# BMS_AFE.net
KiCad netlist of a schematic drawn in Altium Designer
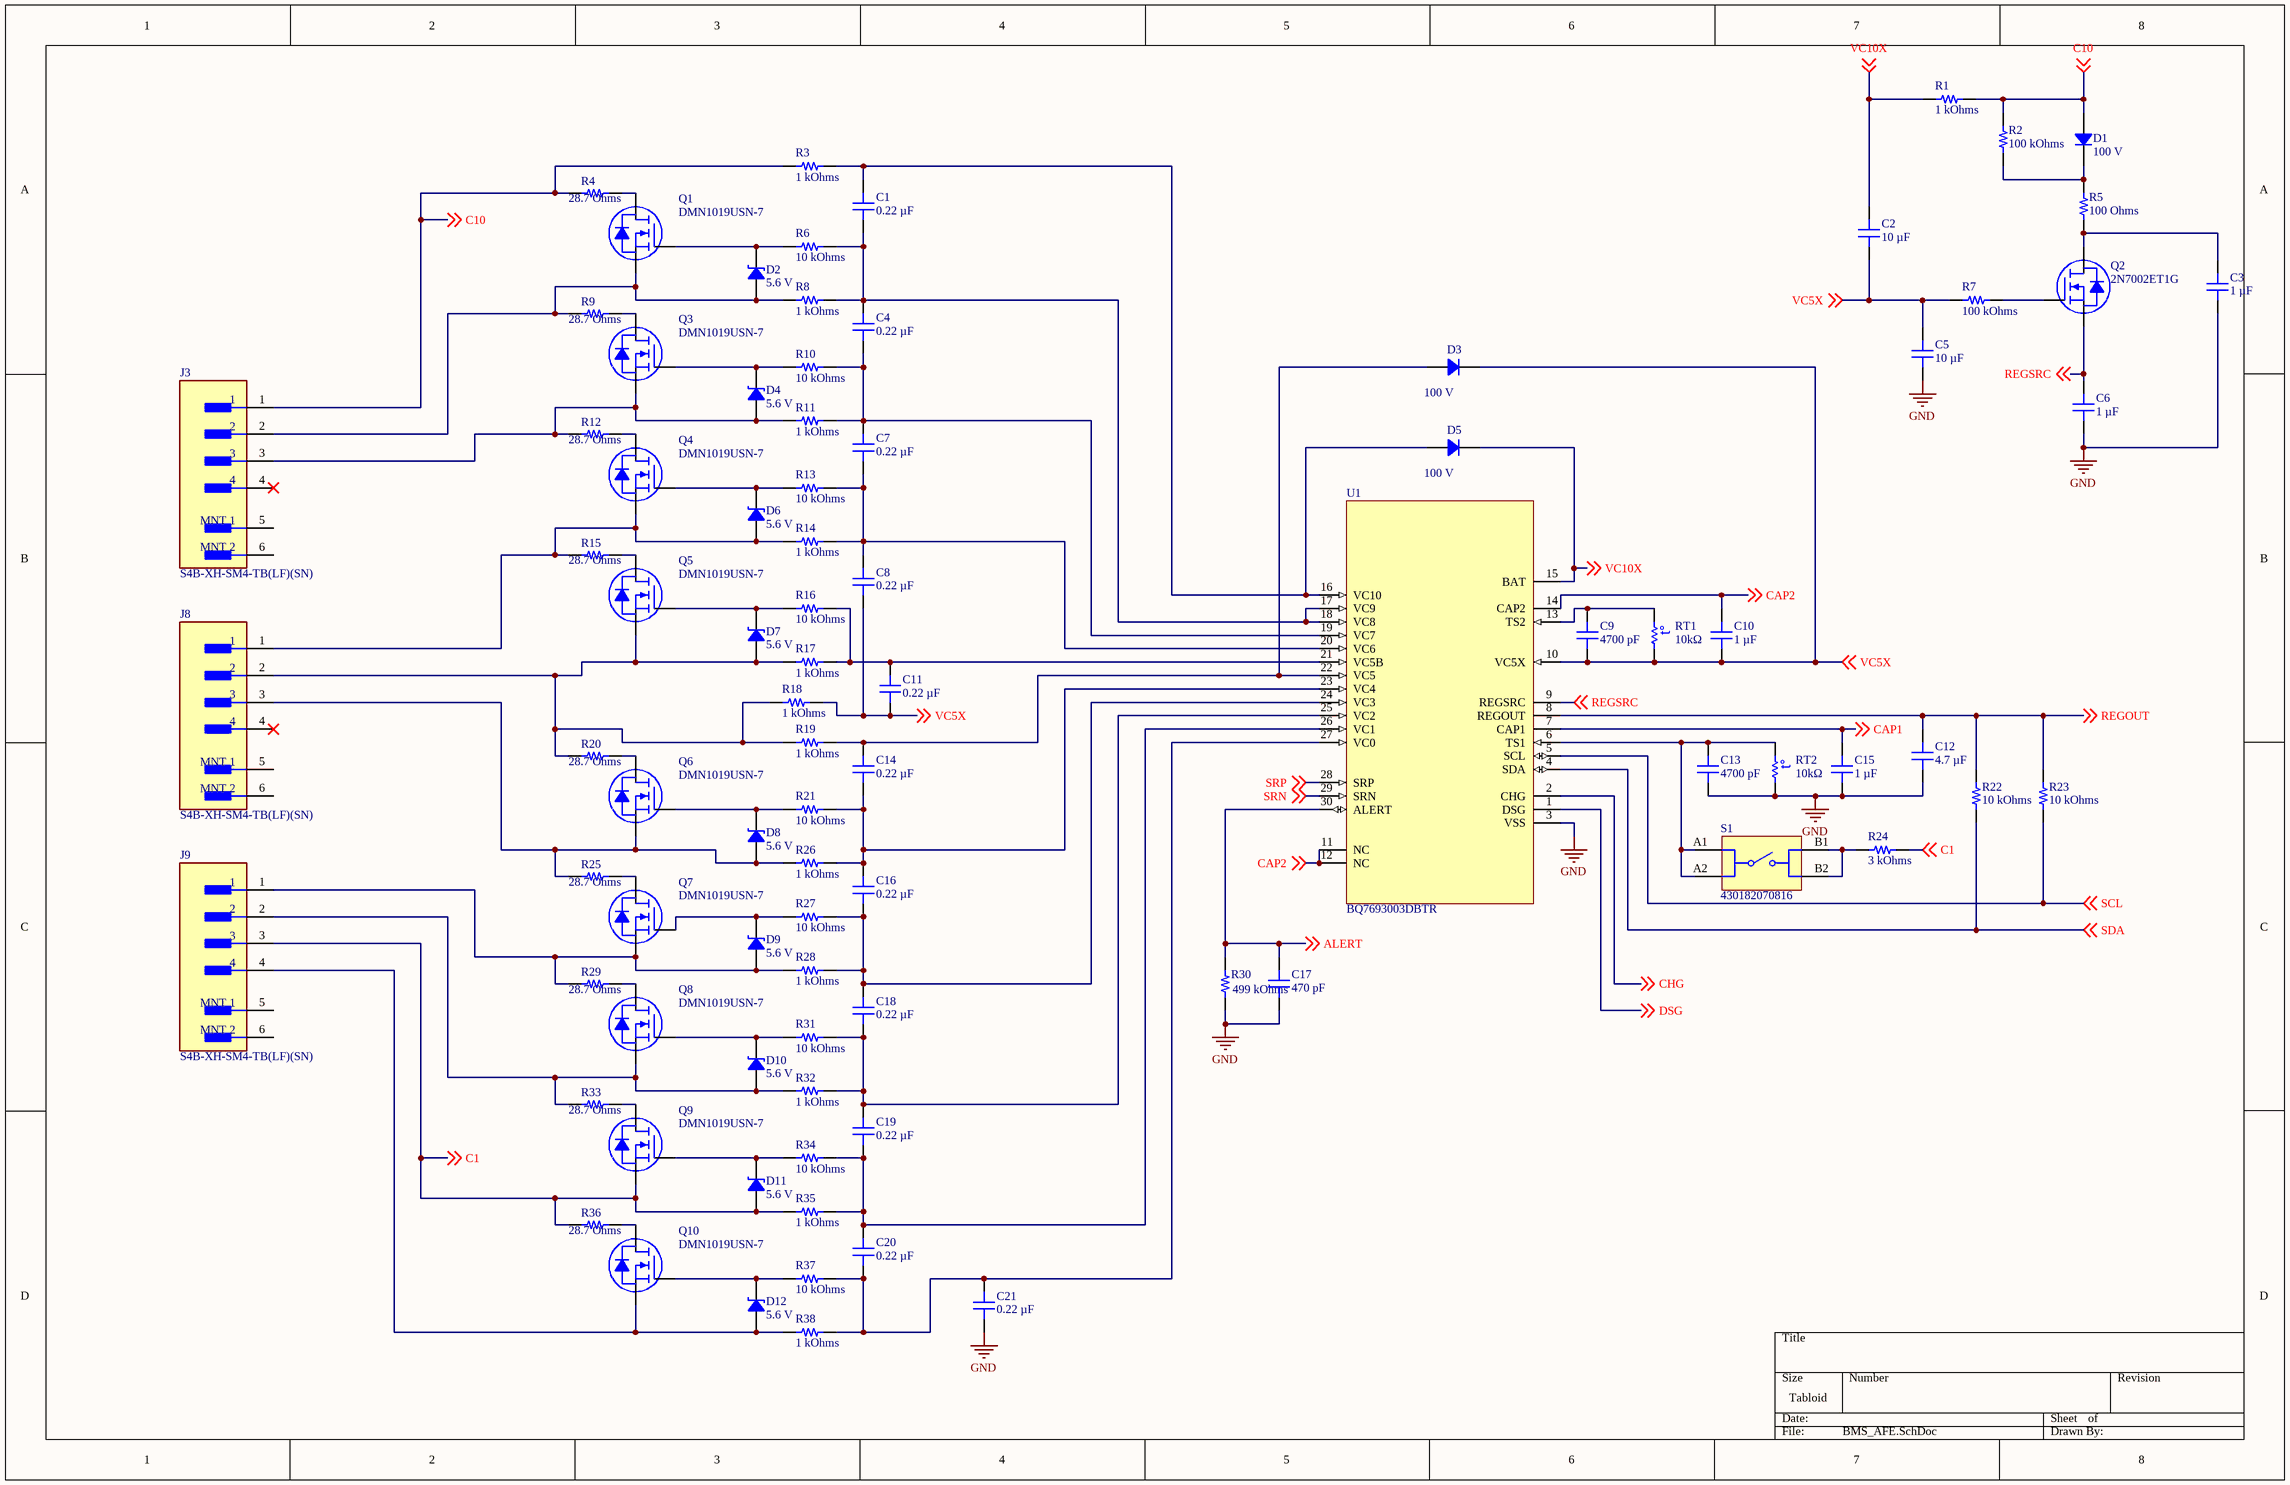
[diagram p0: BMS_AFE.SchDoc]

(export (version "E")
  (design (tool "Eeschema 10.0.6"))
  (components
    (comp (ref "C1")
      (value "0.22 µF")
      (footprint "CAP 0603_1608")
      (description "CAP CER 0.22UF 16V X7R 0603")
      (fields
        (field (name "PART NUMBER") "885012206048")
        (field (name "CAPACITANCE") "0.22 µF")
        (field (name "MANUFACTURER") "Würth Elektronik")
      )
      (libsource (lib "Celestial Altium Library - altium_library") (part "Capacitor"))
    )
    (comp (ref "C2")
      (value "10 µF")
      (footprint "CAP 1210_3225 - 1MM")
      (description "CAP CER 10UF 35V X7R 1210")
      (fields
        (field (name "PART NUMBER") "CL32B106KLJNNNE")
        (field (name "MANUFACTURER") "Samsung Electro-Mechanics")
      )
      (libsource (lib "Celestial Altium Library - altium_library") (part "Capacitor"))
    )
    (comp (ref "C3")
      (value "1 µF")
      (footprint "CAP 0805_2012")
      (description "CAP CER 1UF 50V X7R 0805")
      (fields
        (field (name "PART NUMBER") "GCJ21BR71H105KA01L")
        (field (name "CAPACITANCE") "1 µF")
        (field (name "MANUFACTURER") "Murata Electronics")
      )
      (libsource (lib "Celestial Altium Library - altium_library") (part "Capacitor"))
    )
    (comp (ref "C4")
      (value "0.22 µF")
      (footprint "CAP 0603_1608")
      (description "CAP CER 0.22UF 16V X7R 0603")
      (fields
        (field (name "PART NUMBER") "885012206048")
        (field (name "CAPACITANCE") "0.22 µF")
        (field (name "MANUFACTURER") "Würth Elektronik")
      )
      (libsource (lib "Celestial Altium Library - altium_library") (part "Capacitor"))
    )
    (comp (ref "C5")
      (value "10 µF")
      (footprint "CAP 1210_3225 - 1MM")
      (description "CAP CER 10UF 35V X7R 1210")
      (fields
        (field (name "PART NUMBER") "CL32B106KLJNNNE")
        (field (name "MANUFACTURER") "Samsung Electro-Mechanics")
      )
      (libsource (lib "Celestial Altium Library - altium_library") (part "Capacitor"))
    )
    (comp (ref "C6")
      (value "1 µF")
      (footprint "CAP 0805_2012")
      (description "CAP CER 1UF 50V X7R 0805")
      (fields
        (field (name "PART NUMBER") "GCJ21BR71H105KA01L")
        (field (name "CAPACITANCE") "1 µF")
        (field (name "MANUFACTURER") "Murata Electronics")
      )
      (libsource (lib "Celestial Altium Library - altium_library") (part "Capacitor"))
    )
    (comp (ref "C7")
      (value "0.22 µF")
      (footprint "CAP 0603_1608")
      (description "CAP CER 0.22UF 16V X7R 0603")
      (fields
        (field (name "PART NUMBER") "885012206048")
        (field (name "CAPACITANCE") "0.22 µF")
        (field (name "MANUFACTURER") "Würth Elektronik")
      )
      (libsource (lib "Celestial Altium Library - altium_library") (part "Capacitor"))
    )
    (comp (ref "C8")
      (value "0.22 µF")
      (footprint "CAP 0603_1608")
      (description "CAP CER 0.22UF 16V X7R 0603")
      (fields
        (field (name "PART NUMBER") "885012206048")
        (field (name "CAPACITANCE") "0.22 µF")
        (field (name "MANUFACTURER") "Würth Elektronik")
      )
      (libsource (lib "Celestial Altium Library - altium_library") (part "Capacitor"))
    )
    (comp (ref "C9")
      (value "4700 pF")
      (footprint "CAP 0603_1608")
      (description "CAP CER 4700PF 50V X7R 0603")
      (fields
        (field (name "PART NUMBER") "885012206087")
        (field (name "CAPACITANCE") "4700 pF")
        (field (name "MANUFACTURER") "Würth Elektronik")
      )
      (libsource (lib "Celestial Altium Library - altium_library") (part "Capacitor"))
    )
    (comp (ref "C10")
      (value "1 µF")
      (footprint "CAP 0603_1608")
      (description "CAP CER 1UF 16V X7R 0603")
      (fields
        (field (name "PART NUMBER") "885012206052")
        (field (name "CAPACITANCE") "1 µF")
        (field (name "MANUFACTURER") "Würth Elektronik")
      )
      (libsource (lib "Celestial Altium Library - altium_library") (part "Capacitor"))
    )
    (comp (ref "C11")
      (value "0.22 µF")
      (footprint "CAP 0603_1608")
      (description "CAP CER 0.22UF 16V X7R 0603")
      (fields
        (field (name "PART NUMBER") "885012206048")
        (field (name "CAPACITANCE") "0.22 µF")
        (field (name "MANUFACTURER") "Würth Elektronik")
      )
      (libsource (lib "Celestial Altium Library - altium_library") (part "Capacitor"))
    )
    (comp (ref "C12")
      (value "4.7 µF")
      (footprint "CAP 0805_2012")
      (description "CAP CER 4.7UF 10V X7R 0805")
      (fields
        (field (name "PART NUMBER") "885012207025")
        (field (name "CAPACITANCE") "4.7 µF")
        (field (name "MANUFACTURER") "Würth Elektronik")
      )
      (libsource (lib "Celestial Altium Library - altium_library") (part "Capacitor"))
    )
    (comp (ref "C13")
      (value "4700 pF")
      (footprint "CAP 0603_1608")
      (description "CAP CER 4700PF 50V X7R 0603")
      (fields
        (field (name "PART NUMBER") "885012206087")
        (field (name "CAPACITANCE") "4700 pF")
        (field (name "MANUFACTURER") "Würth Elektronik")
      )
      (libsource (lib "Celestial Altium Library - altium_library") (part "Capacitor"))
    )
    (comp (ref "C14")
      (value "0.22 µF")
      (footprint "CAP 0603_1608")
      (description "CAP CER 0.22UF 16V X7R 0603")
      (fields
        (field (name "PART NUMBER") "885012206048")
        (field (name "CAPACITANCE") "0.22 µF")
        (field (name "MANUFACTURER") "Würth Elektronik")
      )
      (libsource (lib "Celestial Altium Library - altium_library") (part "Capacitor"))
    )
    (comp (ref "C15")
      (value "1 µF")
      (footprint "CAP 0603_1608")
      (description "CAP CER 1UF 16V X7R 0603")
      (fields
        (field (name "PART NUMBER") "885012206052")
        (field (name "CAPACITANCE") "1 µF")
        (field (name "MANUFACTURER") "Würth Elektronik")
      )
      (libsource (lib "Celestial Altium Library - altium_library") (part "Capacitor"))
    )
    (comp (ref "C16")
      (value "0.22 µF")
      (footprint "CAP 0603_1608")
      (description "CAP CER 0.22UF 16V X7R 0603")
      (fields
        (field (name "PART NUMBER") "885012206048")
        (field (name "CAPACITANCE") "0.22 µF")
        (field (name "MANUFACTURER") "Würth Elektronik")
      )
      (libsource (lib "Celestial Altium Library - altium_library") (part "Capacitor"))
    )
    (comp (ref "C17")
      (value "470 pF")
      (footprint "CAP 0603_1608")
      (description "CAP CER 470PF 50V X7R 0603")
      (fields
        (field (name "PART NUMBER") "885012206081")
        (field (name "CAPACITANCE") "470 pF")
        (field (name "MANUFACTURER") "Würth Elektronik")
      )
      (libsource (lib "Celestial Altium Library - altium_library") (part "Capacitor"))
    )
    (comp (ref "C18")
      (value "0.22 µF")
      (footprint "CAP 0603_1608")
      (description "CAP CER 0.22UF 16V X7R 0603")
      (fields
        (field (name "PART NUMBER") "885012206048")
        (field (name "CAPACITANCE") "0.22 µF")
        (field (name "MANUFACTURER") "Würth Elektronik")
      )
      (libsource (lib "Celestial Altium Library - altium_library") (part "Capacitor"))
    )
    (comp (ref "C19")
      (value "0.22 µF")
      (footprint "CAP 0603_1608")
      (description "CAP CER 0.22UF 16V X7R 0603")
      (fields
        (field (name "PART NUMBER") "885012206048")
        (field (name "CAPACITANCE") "0.22 µF")
        (field (name "MANUFACTURER") "Würth Elektronik")
      )
      (libsource (lib "Celestial Altium Library - altium_library") (part "Capacitor"))
    )
    (comp (ref "C20")
      (value "0.22 µF")
      (footprint "CAP 0603_1608")
      (description "CAP CER 0.22UF 16V X7R 0603")
      (fields
        (field (name "PART NUMBER") "885012206048")
        (field (name "CAPACITANCE") "0.22 µF")
        (field (name "MANUFACTURER") "Würth Elektronik")
      )
      (libsource (lib "Celestial Altium Library - altium_library") (part "Capacitor"))
    )
    (comp (ref "C21")
      (value "0.22 µF")
      (footprint "CAP 0603_1608")
      (description "CAP CER 0.22UF 16V X7R 0603")
      (fields
        (field (name "PART NUMBER") "885012206048")
        (field (name "CAPACITANCE") "0.22 µF")
        (field (name "MANUFACTURER") "Würth Elektronik")
      )
      (libsource (lib "Celestial Altium Library - altium_library") (part "Capacitor"))
    )
    (comp (ref "D1")
      (value "1N4148W-7-F")
      (footprint "SOD-123")
      (description "DIODE GEN PURP 100V 300MA SOD123")
      (fields
        (field (name "MANUFACTURER") "Diodes Incorporated")
        (field (name "VOLTAGE - DC REVERSE (VR) (MAX)") "100 V")
      )
      (libsource (lib "Celestial Altium Library - altium_library") (part "Diode"))
    )
    (comp (ref "D2")
      (value "MMSZ5232BS-7-F")
      (footprint "SOD323")
      (description "DIODE ZENER 5.6V 200MW SOD323")
      (fields
        (field (name "MANUFACTURER") "Diodes Incorporated")
        (field (name "TOLERANCE") "±5%")
        (field (name "VOLTAGE - ZENER (NOM) (VZ)") "5.6 V")
      )
      (libsource (lib "Celestial Altium Library - altium_library") (part "Diode Zener"))
    )
    (comp (ref "D3")
      (value "1N4148W-7-F")
      (footprint "SOD-123")
      (description "DIODE GEN PURP 100V 300MA SOD123")
      (fields
        (field (name "MANUFACTURER") "Diodes Incorporated")
        (field (name "VOLTAGE - DC REVERSE (VR) (MAX)") "100 V")
      )
      (libsource (lib "Celestial Altium Library - altium_library") (part "Diode"))
    )
    (comp (ref "D4")
      (value "MMSZ5232BS-7-F")
      (footprint "SOD323")
      (description "DIODE ZENER 5.6V 200MW SOD323")
      (fields
        (field (name "MANUFACTURER") "Diodes Incorporated")
        (field (name "TOLERANCE") "±5%")
        (field (name "VOLTAGE - ZENER (NOM) (VZ)") "5.6 V")
      )
      (libsource (lib "Celestial Altium Library - altium_library") (part "Diode Zener"))
    )
    (comp (ref "D5")
      (value "1N4148W-7-F")
      (footprint "SOD-123")
      (description "DIODE GEN PURP 100V 300MA SOD123")
      (fields
        (field (name "MANUFACTURER") "Diodes Incorporated")
        (field (name "VOLTAGE - DC REVERSE (VR) (MAX)") "100 V")
      )
      (libsource (lib "Celestial Altium Library - altium_library") (part "Diode"))
    )
    (comp (ref "D6")
      (value "MMSZ5232BS-7-F")
      (footprint "SOD323")
      (description "DIODE ZENER 5.6V 200MW SOD323")
      (fields
        (field (name "MANUFACTURER") "Diodes Incorporated")
        (field (name "TOLERANCE") "±5%")
        (field (name "VOLTAGE - ZENER (NOM) (VZ)") "5.6 V")
      )
      (libsource (lib "Celestial Altium Library - altium_library") (part "Diode Zener"))
    )
    (comp (ref "D7")
      (value "MMSZ5232BS-7-F")
      (footprint "SOD323")
      (description "DIODE ZENER 5.6V 200MW SOD323")
      (fields
        (field (name "MANUFACTURER") "Diodes Incorporated")
        (field (name "TOLERANCE") "±5%")
        (field (name "VOLTAGE - ZENER (NOM) (VZ)") "5.6 V")
      )
      (libsource (lib "Celestial Altium Library - altium_library") (part "Diode Zener"))
    )
    (comp (ref "D8")
      (value "MMSZ5232BS-7-F")
      (footprint "SOD323")
      (description "DIODE ZENER 5.6V 200MW SOD323")
      (fields
        (field (name "MANUFACTURER") "Diodes Incorporated")
        (field (name "TOLERANCE") "±5%")
        (field (name "VOLTAGE - ZENER (NOM) (VZ)") "5.6 V")
      )
      (libsource (lib "Celestial Altium Library - altium_library") (part "Diode Zener"))
    )
    (comp (ref "D9")
      (value "MMSZ5232BS-7-F")
      (footprint "SOD323")
      (description "DIODE ZENER 5.6V 200MW SOD323")
      (fields
        (field (name "MANUFACTURER") "Diodes Incorporated")
        (field (name "TOLERANCE") "±5%")
        (field (name "VOLTAGE - ZENER (NOM) (VZ)") "5.6 V")
      )
      (libsource (lib "Celestial Altium Library - altium_library") (part "Diode Zener"))
    )
    (comp (ref "D10")
      (value "MMSZ5232BS-7-F")
      (footprint "SOD323")
      (description "DIODE ZENER 5.6V 200MW SOD323")
      (fields
        (field (name "MANUFACTURER") "Diodes Incorporated")
        (field (name "TOLERANCE") "±5%")
        (field (name "VOLTAGE - ZENER (NOM) (VZ)") "5.6 V")
      )
      (libsource (lib "Celestial Altium Library - altium_library") (part "Diode Zener"))
    )
    (comp (ref "D11")
      (value "MMSZ5232BS-7-F")
      (footprint "SOD323")
      (description "DIODE ZENER 5.6V 200MW SOD323")
      (fields
        (field (name "MANUFACTURER") "Diodes Incorporated")
        (field (name "TOLERANCE") "±5%")
        (field (name "VOLTAGE - ZENER (NOM) (VZ)") "5.6 V")
      )
      (libsource (lib "Celestial Altium Library - altium_library") (part "Diode Zener"))
    )
    (comp (ref "D12")
      (value "MMSZ5232BS-7-F")
      (footprint "SOD323")
      (description "DIODE ZENER 5.6V 200MW SOD323")
      (fields
        (field (name "MANUFACTURER") "Diodes Incorporated")
        (field (name "TOLERANCE") "±5%")
        (field (name "VOLTAGE - ZENER (NOM) (VZ)") "5.6 V")
      )
      (libsource (lib "Celestial Altium Library - altium_library") (part "Diode Zener"))
    )
    (comp (ref "J3")
      (value "S4B-XH-SM4-TB(LF)(SN)")
      (footprint "FP-S4B-XH-SM4-TB_LF_SN-MFG")
      (description "CONN HEADER SMD R/A 4POS 2.5MM")
      (libsource (lib "BMS_AFE") (part "S4B-XH-SM4-TB"))
    )
    (comp (ref "J8")
      (value "S4B-XH-SM4-TB(LF)(SN)")
      (footprint "FP-S4B-XH-SM4-TB_LF_SN-MFG")
      (description "CONN HEADER SMD R/A 4POS 2.5MM")
      (libsource (lib "BMS_AFE") (part "S4B-XH-SM4-TB"))
    )
    (comp (ref "J9")
      (value "S4B-XH-SM4-TB(LF)(SN)")
      (footprint "FP-S4B-XH-SM4-TB_LF_SN-MFG")
      (description "CONN HEADER SMD R/A 4POS 2.5MM")
      (libsource (lib "BMS_AFE") (part "S4B-XH-SM4-TB"))
    )
    (comp (ref "Q1")
      (value "DMN1019USN-7")
      (footprint "DIODES SOT-23-3")
      (description "MOSFET N-CH 12V 9.3A SC59")
      (fields (field (name "MANUFACTURER") "Diodes Incorporated"))
      (libsource (lib "Celestial Altium Library - altium_library") (part "DIODES INC MOSFET N-CH SOT-23-3"))
    )
    (comp (ref "Q2")
      (value "2N7002ET1G")
      (footprint "ON SEMI SOT-23-3")
      (description "MOSFET N-CH 60V 260MA SOT-23")
      (fields (field (name "MANUFACTURER") "ON Semiconductor"))
      (libsource (lib "Celestial Altium Library - altium_library") (part "ON SEMI MOSFET N-CH SOT-23-3"))
    )
    (comp (ref "Q3")
      (value "DMN1019USN-7")
      (footprint "DIODES SOT-23-3")
      (description "MOSFET N-CH 12V 9.3A SC59")
      (fields (field (name "MANUFACTURER") "Diodes Incorporated"))
      (libsource (lib "Celestial Altium Library - altium_library") (part "DIODES INC MOSFET N-CH SOT-23-3"))
    )
    (comp (ref "Q4")
      (value "DMN1019USN-7")
      (footprint "DIODES SOT-23-3")
      (description "MOSFET N-CH 12V 9.3A SC59")
      (fields (field (name "MANUFACTURER") "Diodes Incorporated"))
      (libsource (lib "Celestial Altium Library - altium_library") (part "DIODES INC MOSFET N-CH SOT-23-3"))
    )
    (comp (ref "Q5")
      (value "DMN1019USN-7")
      (footprint "DIODES SOT-23-3")
      (description "MOSFET N-CH 12V 9.3A SC59")
      (fields (field (name "MANUFACTURER") "Diodes Incorporated"))
      (libsource (lib "Celestial Altium Library - altium_library") (part "DIODES INC MOSFET N-CH SOT-23-3"))
    )
    (comp (ref "Q6")
      (value "DMN1019USN-7")
      (footprint "DIODES SOT-23-3")
      (description "MOSFET N-CH 12V 9.3A SC59")
      (fields (field (name "MANUFACTURER") "Diodes Incorporated"))
      (libsource (lib "Celestial Altium Library - altium_library") (part "DIODES INC MOSFET N-CH SOT-23-3"))
    )
    (comp (ref "Q7")
      (value "DMN1019USN-7")
      (footprint "DIODES SOT-23-3")
      (description "MOSFET N-CH 12V 9.3A SC59")
      (fields (field (name "MANUFACTURER") "Diodes Incorporated"))
      (libsource (lib "Celestial Altium Library - altium_library") (part "DIODES INC MOSFET N-CH SOT-23-3"))
    )
    (comp (ref "Q8")
      (value "DMN1019USN-7")
      (footprint "DIODES SOT-23-3")
      (description "MOSFET N-CH 12V 9.3A SC59")
      (fields (field (name "MANUFACTURER") "Diodes Incorporated"))
      (libsource (lib "Celestial Altium Library - altium_library") (part "DIODES INC MOSFET N-CH SOT-23-3"))
    )
    (comp (ref "Q9")
      (value "DMN1019USN-7")
      (footprint "DIODES SOT-23-3")
      (description "MOSFET N-CH 12V 9.3A SC59")
      (fields (field (name "MANUFACTURER") "Diodes Incorporated"))
      (libsource (lib "Celestial Altium Library - altium_library") (part "DIODES INC MOSFET N-CH SOT-23-3"))
    )
    (comp (ref "Q10")
      (value "DMN1019USN-7")
      (footprint "DIODES SOT-23-3")
      (description "MOSFET N-CH 12V 9.3A SC59")
      (fields (field (name "MANUFACTURER") "Diodes Incorporated"))
      (libsource (lib "Celestial Altium Library - altium_library") (part "DIODES INC MOSFET N-CH SOT-23-3"))
    )
    (comp (ref "R1")
      (value "1 kOhms")
      (footprint "RES 0603_1608")
      (description "RES SMD 1K OHM 5% 1/10W 0603")
      (fields (field (name "PART NUMBER") "CRCW06031K00JNEA") (field (name "MANUFACTURER") "Vishay Dale"))
      (libsource (lib "Celestial Altium Library - altium_library") (part "Resistor"))
    )
    (comp (ref "R2")
      (value "100 kOhms")
      (footprint "RES 0805_2012")
      (description "RES SMD 100K OHM 1% 1/8W 0805")
      (fields (field (name "PART NUMBER") "CRCW0805100KFKEA") (field (name "MANUFACTURER") "Vishay Dale"))
      (libsource (lib "Celestial Altium Library - altium_library") (part "Resistor"))
    )
    (comp (ref "R3")
      (value "1 kOhms")
      (footprint "RES 0603_1608")
      (description "RES SMD 1K OHM 5% 1/10W 0603")
      (fields (field (name "PART NUMBER") "CRCW06031K00JNEA") (field (name "MANUFACTURER") "Vishay Dale"))
      (libsource (lib "Celestial Altium Library - altium_library") (part "Resistor"))
    )
    (comp (ref "R4")
      (value "28.7 Ohms")
      (footprint "RES 2512_6432")
      (description "RES SMD 28.7 OHM 1% 1W 2512")
      (fields
        (field (name "MANUFACTURER") "Vishay Dale")
        (field (name "PART NUMBER") "CRCW251228R7FKEG")
        (field (name "RESISTANCE") "28.7 Ohms")
      )
      (libsource (lib "Celestial Altium Library - altium_library") (part "Resistor"))
    )
    (comp (ref "R5")
      (value "100 Ohms")
      (footprint "RES 0805_2012")
      (description "RES SMD 100 OHM 1% 1/8W 0805")
      (fields (field (name "PART NUMBER") "CRCW0805100RFKEA") (field (name "MANUFACTURER") "Vishay Dale"))
      (libsource (lib "Celestial Altium Library - altium_library") (part "Resistor"))
    )
    (comp (ref "R6")
      (value "10 kOhms")
      (footprint "RES 0603_1608")
      (description "RES SMD 10K OHM 5% 1/10W 0603")
      (fields (field (name "PART NUMBER") "CRCW060310K0JNEA") (field (name "MANUFACTURER") "Vishay Dale"))
      (libsource (lib "Celestial Altium Library - altium_library") (part "Resistor"))
    )
    (comp (ref "R7")
      (value "100 kOhms")
      (footprint "RES 0805_2012")
      (description "RES SMD 100K OHM 1% 1/8W 0805")
      (fields (field (name "PART NUMBER") "CRCW0805100KFKEA") (field (name "MANUFACTURER") "Vishay Dale"))
      (libsource (lib "Celestial Altium Library - altium_library") (part "Resistor"))
    )
    (comp (ref "R8")
      (value "1 kOhms")
      (footprint "RES 0603_1608")
      (description "RES SMD 1K OHM 5% 1/10W 0603")
      (fields (field (name "PART NUMBER") "CRCW06031K00JNEA") (field (name "MANUFACTURER") "Vishay Dale"))
      (libsource (lib "Celestial Altium Library - altium_library") (part "Resistor"))
    )
    (comp (ref "R9")
      (value "28.7 Ohms")
      (footprint "RES 2512_6432")
      (description "RES SMD 28.7 OHM 1% 1W 2512")
      (fields
        (field (name "MANUFACTURER") "Vishay Dale")
        (field (name "PART NUMBER") "CRCW251228R7FKEG")
        (field (name "RESISTANCE") "28.7 Ohms")
      )
      (libsource (lib "Celestial Altium Library - altium_library") (part "Resistor"))
    )
    (comp (ref "R10")
      (value "10 kOhms")
      (footprint "RES 0603_1608")
      (description "RES SMD 10K OHM 5% 1/10W 0603")
      (fields (field (name "PART NUMBER") "CRCW060310K0JNEA") (field (name "MANUFACTURER") "Vishay Dale"))
      (libsource (lib "Celestial Altium Library - altium_library") (part "Resistor"))
    )
    (comp (ref "R11")
      (value "1 kOhms")
      (footprint "RES 0603_1608")
      (description "RES SMD 1K OHM 5% 1/10W 0603")
      (fields (field (name "PART NUMBER") "CRCW06031K00JNEA") (field (name "MANUFACTURER") "Vishay Dale"))
      (libsource (lib "Celestial Altium Library - altium_library") (part "Resistor"))
    )
    (comp (ref "R12")
      (value "28.7 Ohms")
      (footprint "RES 2512_6432")
      (description "RES SMD 28.7 OHM 1% 1W 2512")
      (fields
        (field (name "MANUFACTURER") "Vishay Dale")
        (field (name "PART NUMBER") "CRCW251228R7FKEG")
        (field (name "RESISTANCE") "28.7 Ohms")
      )
      (libsource (lib "Celestial Altium Library - altium_library") (part "Resistor"))
    )
    (comp (ref "R13")
      (value "10 kOhms")
      (footprint "RES 0603_1608")
      (description "RES SMD 10K OHM 5% 1/10W 0603")
      (fields (field (name "PART NUMBER") "CRCW060310K0JNEA") (field (name "MANUFACTURER") "Vishay Dale"))
      (libsource (lib "Celestial Altium Library - altium_library") (part "Resistor"))
    )
    (comp (ref "R14")
      (value "1 kOhms")
      (footprint "RES 0603_1608")
      (description "RES SMD 1K OHM 5% 1/10W 0603")
      (fields (field (name "PART NUMBER") "CRCW06031K00JNEA") (field (name "MANUFACTURER") "Vishay Dale"))
      (libsource (lib "Celestial Altium Library - altium_library") (part "Resistor"))
    )
    (comp (ref "R15")
      (value "28.7 Ohms")
      (footprint "RES 2512_6432")
      (description "RES SMD 28.7 OHM 1% 1W 2512")
      (fields
        (field (name "MANUFACTURER") "Vishay Dale")
        (field (name "PART NUMBER") "CRCW251228R7FKEG")
        (field (name "RESISTANCE") "28.7 Ohms")
      )
      (libsource (lib "Celestial Altium Library - altium_library") (part "Resistor"))
    )
    (comp (ref "R16")
      (value "10 kOhms")
      (footprint "RES 0603_1608")
      (description "RES SMD 10K OHM 5% 1/10W 0603")
      (fields (field (name "PART NUMBER") "CRCW060310K0JNEA") (field (name "MANUFACTURER") "Vishay Dale"))
      (libsource (lib "Celestial Altium Library - altium_library") (part "Resistor"))
    )
    (comp (ref "R17")
      (value "1 kOhms")
      (footprint "RES 0603_1608")
      (description "RES SMD 1K OHM 5% 1/10W 0603")
      (fields (field (name "PART NUMBER") "CRCW06031K00JNEA") (field (name "MANUFACTURER") "Vishay Dale"))
      (libsource (lib "Celestial Altium Library - altium_library") (part "Resistor"))
    )
    (comp (ref "R18")
      (value "1 kOhms")
      (footprint "RES 0603_1608")
      (description "RES SMD 1K OHM 5% 1/10W 0603")
      (fields (field (name "PART NUMBER") "CRCW06031K00JNEA") (field (name "MANUFACTURER") "Vishay Dale"))
      (libsource (lib "Celestial Altium Library - altium_library") (part "Resistor"))
    )
    (comp (ref "R19")
      (value "1 kOhms")
      (footprint "RES 0603_1608")
      (description "RES SMD 1K OHM 5% 1/10W 0603")
      (fields (field (name "PART NUMBER") "CRCW06031K00JNEA") (field (name "MANUFACTURER") "Vishay Dale"))
      (libsource (lib "Celestial Altium Library - altium_library") (part "Resistor"))
    )
    (comp (ref "R20")
      (value "28.7 Ohms")
      (footprint "RES 2512_6432")
      (description "RES SMD 28.7 OHM 1% 1W 2512")
      (fields
        (field (name "MANUFACTURER") "Vishay Dale")
        (field (name "PART NUMBER") "CRCW251228R7FKEG")
        (field (name "RESISTANCE") "28.7 Ohms")
      )
      (libsource (lib "Celestial Altium Library - altium_library") (part "Resistor"))
    )
    (comp (ref "R21")
      (value "10 kOhms")
      (footprint "RES 0603_1608")
      (description "RES SMD 10K OHM 5% 1/10W 0603")
      (fields (field (name "PART NUMBER") "CRCW060310K0JNEA") (field (name "MANUFACTURER") "Vishay Dale"))
      (libsource (lib "Celestial Altium Library - altium_library") (part "Resistor"))
    )
    (comp (ref "R22")
      (value "10 kOhms")
      (footprint "RES 0603_1608")
      (description "RES SMD 10K OHM 5% 1/10W 0603")
      (fields (field (name "PART NUMBER") "CRCW060310K0JNEA") (field (name "MANUFACTURER") "Vishay Dale"))
      (libsource (lib "Celestial Altium Library - altium_library") (part "Resistor"))
    )
    (comp (ref "R23")
      (value "10 kOhms")
      (footprint "RES 0603_1608")
      (description "RES SMD 10K OHM 5% 1/10W 0603")
      (fields (field (name "PART NUMBER") "CRCW060310K0JNEA") (field (name "MANUFACTURER") "Vishay Dale"))
      (libsource (lib "Celestial Altium Library - altium_library") (part "Resistor"))
    )
    (comp (ref "R24")
      (value "3 kOhms")
      (footprint "RES 0603_1608")
      (description "RES SMD 3K OHM 5% 1/10W 0603")
      (fields (field (name "PART NUMBER") "CRCW06033K00JNEA") (field (name "MANUFACTURER") "Vishay Dale"))
      (libsource (lib "Celestial Altium Library - altium_library") (part "Resistor"))
    )
    (comp (ref "R25")
      (value "28.7 Ohms")
      (footprint "RES 2512_6432")
      (description "RES SMD 28.7 OHM 1% 1W 2512")
      (fields
        (field (name "MANUFACTURER") "Vishay Dale")
        (field (name "PART NUMBER") "CRCW251228R7FKEG")
        (field (name "RESISTANCE") "28.7 Ohms")
      )
      (libsource (lib "Celestial Altium Library - altium_library") (part "Resistor"))
    )
    (comp (ref "R26")
      (value "1 kOhms")
      (footprint "RES 0603_1608")
      (description "RES SMD 1K OHM 5% 1/10W 0603")
      (fields (field (name "PART NUMBER") "CRCW06031K00JNEA") (field (name "MANUFACTURER") "Vishay Dale"))
      (libsource (lib "Celestial Altium Library - altium_library") (part "Resistor"))
    )
    (comp (ref "R27")
      (value "10 kOhms")
      (footprint "RES 0603_1608")
      (description "RES SMD 10K OHM 5% 1/10W 0603")
      (fields (field (name "PART NUMBER") "CRCW060310K0JNEA") (field (name "MANUFACTURER") "Vishay Dale"))
      (libsource (lib "Celestial Altium Library - altium_library") (part "Resistor"))
    )
    (comp (ref "R28")
      (value "1 kOhms")
      (footprint "RES 0603_1608")
      (description "RES SMD 1K OHM 5% 1/10W 0603")
      (fields (field (name "PART NUMBER") "CRCW06031K00JNEA") (field (name "MANUFACTURER") "Vishay Dale"))
      (libsource (lib "Celestial Altium Library - altium_library") (part "Resistor"))
    )
    (comp (ref "R29")
      (value "28.7 Ohms")
      (footprint "RES 2512_6432")
      (description "RES SMD 28.7 OHM 1% 1W 2512")
      (fields
        (field (name "MANUFACTURER") "Vishay Dale")
        (field (name "PART NUMBER") "CRCW251228R7FKEG")
        (field (name "RESISTANCE") "28.7 Ohms")
      )
      (libsource (lib "Celestial Altium Library - altium_library") (part "Resistor"))
    )
    (comp (ref "R30")
      (value "499 kOhms")
      (footprint "RES 0603_1608")
      (description "RES SMD 499K OHM 1% 1/3W 0603")
      (fields (field (name "PART NUMBER") "CRCW0603499KFKEAHP") (field (name "MANUFACTURER") "Vishay Dale"))
      (libsource (lib "Celestial Altium Library - altium_library") (part "Resistor"))
    )
    (comp (ref "R31")
      (value "10 kOhms")
      (footprint "RES 0603_1608")
      (description "RES SMD 10K OHM 5% 1/10W 0603")
      (fields (field (name "PART NUMBER") "CRCW060310K0JNEA") (field (name "MANUFACTURER") "Vishay Dale"))
      (libsource (lib "Celestial Altium Library - altium_library") (part "Resistor"))
    )
    (comp (ref "R32")
      (value "1 kOhms")
      (footprint "RES 0603_1608")
      (description "RES SMD 1K OHM 5% 1/10W 0603")
      (fields (field (name "PART NUMBER") "CRCW06031K00JNEA") (field (name "MANUFACTURER") "Vishay Dale"))
      (libsource (lib "Celestial Altium Library - altium_library") (part "Resistor"))
    )
    (comp (ref "R33")
      (value "28.7 Ohms")
      (footprint "RES 2512_6432")
      (description "RES SMD 28.7 OHM 1% 1W 2512")
      (fields
        (field (name "MANUFACTURER") "Vishay Dale")
        (field (name "PART NUMBER") "CRCW251228R7FKEG")
        (field (name "RESISTANCE") "28.7 Ohms")
      )
      (libsource (lib "Celestial Altium Library - altium_library") (part "Resistor"))
    )
    (comp (ref "R34")
      (value "10 kOhms")
      (footprint "RES 0603_1608")
      (description "RES SMD 10K OHM 5% 1/10W 0603")
      (fields (field (name "PART NUMBER") "CRCW060310K0JNEA") (field (name "MANUFACTURER") "Vishay Dale"))
      (libsource (lib "Celestial Altium Library - altium_library") (part "Resistor"))
    )
    (comp (ref "R35")
      (value "1 kOhms")
      (footprint "RES 0603_1608")
      (description "RES SMD 1K OHM 5% 1/10W 0603")
      (fields (field (name "PART NUMBER") "CRCW06031K00JNEA") (field (name "MANUFACTURER") "Vishay Dale"))
      (libsource (lib "Celestial Altium Library - altium_library") (part "Resistor"))
    )
    (comp (ref "R36")
      (value "28.7 Ohms")
      (footprint "RES 2512_6432")
      (description "RES SMD 28.7 OHM 1% 1W 2512")
      (fields
        (field (name "MANUFACTURER") "Vishay Dale")
        (field (name "PART NUMBER") "CRCW251228R7FKEG")
        (field (name "RESISTANCE") "28.7 Ohms")
      )
      (libsource (lib "Celestial Altium Library - altium_library") (part "Resistor"))
    )
    (comp (ref "R37")
      (value "10 kOhms")
      (footprint "RES 0603_1608")
      (description "RES SMD 10K OHM 5% 1/10W 0603")
      (fields (field (name "PART NUMBER") "CRCW060310K0JNEA") (field (name "MANUFACTURER") "Vishay Dale"))
      (libsource (lib "Celestial Altium Library - altium_library") (part "Resistor"))
    )
    (comp (ref "R38")
      (value "1 kOhms")
      (footprint "RES 0603_1608")
      (description "RES SMD 1K OHM 5% 1/10W 0603")
      (fields (field (name "PART NUMBER") "CRCW06031K00JNEA") (field (name "MANUFACTURER") "Vishay Dale"))
      (libsource (lib "Celestial Altium Library - altium_library") (part "Resistor"))
    )
    (comp (ref "RT1")
      (value "103AT-2")
      (footprint "FP-103AT-2-MFG")
      (description "Thermistor NTC 10KOhm 1% 2-Pin")
      (fields (field (name "TOLERANCE") "1%") (field (name "RESISTANCE") "10kΩ"))
      (libsource (lib "BMS_AFE") (part "103AT-2"))
    )
    (comp (ref "RT2")
      (value "103AT-2")
      (footprint "FP-103AT-2-MFG")
      (description "Thermistor NTC 10KOhm 1% 2-Pin")
      (fields (field (name "TOLERANCE") "1%") (field (name "RESISTANCE") "10kΩ"))
      (libsource (lib "BMS_AFE") (part "103AT-2"))
    )
    (comp (ref "S1")
      (value "430182070816")
      (footprint "430182070816")
      (description "Switch Tactile Spst-no 0.05A 12V")
      (libsource (lib "BMS_AFE") (part "430182070816"))
    )
    (comp (ref "U1")
      (value "BQ7693003DBTR")
      (footprint "FP-DBT0030A-IPC_C")
      (description "IC BATT MGMT LI-ION AFE 30TSSOP")
      (fields
        (field (name "OCTOPART") "https://octopart.com/bq7693003dbtr-texas+instruments-34472212")
        (field (name "MANUFACTURER") "Texas Instruments")
      )
      (libsource (lib "BMS_AFE") (part "BQ7693003DBTR"))
    )
  )
  (nets
    (net (code "1") (name "ALERT") (class "Default")
      (node (ref "C17") (pin "2") (pinfunction "2_2") (pintype "passive"))
      (node (ref "R30") (pin "2") (pinfunction "2_2") (pintype "passive"))
      (node (ref "U1") (pin "30") (pinfunction "ALERT_30") (pintype "bidirectional"))
    )
    (net (code "2") (name "C1") (class "Default")
      (node (ref "D11") (pin "1") (pinfunction "1_1") (pintype "passive"))
      (node (ref "J9") (pin "3") (pinfunction "3_3") (pintype "passive"))
      (node (ref "Q9") (pin "2") (pinfunction "S_2") (pintype "passive"))
      (node (ref "R24") (pin "2") (pinfunction "2_2") (pintype "passive"))
      (node (ref "R35") (pin "1") (pinfunction "1_1") (pintype "passive"))
      (node (ref "R36") (pin "1") (pinfunction "1_1") (pintype "passive"))
    )
    (net (code "3") (name "C10") (class "Default")
      (node (ref "D1") (pin "1") (pinfunction "1_1") (pintype "passive"))
      (node (ref "J3") (pin "1") (pinfunction "1_1") (pintype "passive"))
      (node (ref "R1") (pin "2") (pinfunction "2_2") (pintype "passive"))
      (node (ref "R2") (pin "2") (pinfunction "2_2") (pintype "passive"))
      (node (ref "R3") (pin "1") (pinfunction "1_1") (pintype "passive"))
      (node (ref "R4") (pin "1") (pinfunction "1_1") (pintype "passive"))
    )
    (net (code "4") (name "CAP1") (class "Default")
      (node (ref "C15") (pin "1") (pinfunction "1_1") (pintype "passive"))
      (node (ref "U1") (pin "7") (pinfunction "CAP1_7") (pintype "passive"))
    )
    (net (code "5") (name "CAP2") (class "Default")
      (node (ref "C10") (pin "1") (pinfunction "1_1") (pintype "passive"))
      (node (ref "U1") (pin "11") (pinfunction "NC_11") (pintype "passive"))
      (node (ref "U1") (pin "12") (pinfunction "NC_12") (pintype "passive"))
      (node (ref "U1") (pin "14") (pinfunction "CAP2_14") (pintype "passive"))
    )
    (net (code "6") (name "CHG") (class "Default")
      (node (ref "U1") (pin "2") (pinfunction "CHG_2") (pintype "power_in"))
    )
    (net (code "7") (name "DSG") (class "Default")
      (node (ref "U1") (pin "1") (pinfunction "DSG_1") (pintype "power_in"))
    )
    (net (code "8") (name "GND") (class "Default")
      (node (ref "C12") (pin "1") (pinfunction "1_1") (pintype "passive"))
      (node (ref "C13") (pin "1") (pinfunction "1_1") (pintype "passive"))
      (node (ref "C15") (pin "2") (pinfunction "2_2") (pintype "passive"))
      (node (ref "C17") (pin "1") (pinfunction "1_1") (pintype "passive"))
      (node (ref "C21") (pin "1") (pinfunction "1_1") (pintype "passive"))
      (node (ref "C3") (pin "1") (pinfunction "1_1") (pintype "passive"))
      (node (ref "C5") (pin "1") (pinfunction "1_1") (pintype "passive"))
      (node (ref "C6") (pin "1") (pinfunction "1_1") (pintype "passive"))
      (node (ref "R30") (pin "1") (pinfunction "1_1") (pintype "passive"))
      (node (ref "RT2") (pin "1") (pinfunction "1_1") (pintype "passive"))
      (node (ref "U1") (pin "3") (pinfunction "VSS_3") (pintype "power_in"))
    )
    (net (code "9") (name "Net-(D1-Pad2)") (class "Default")
      (node (ref "D1") (pin "2") (pinfunction "2_2") (pintype "passive"))
      (node (ref "R2") (pin "1") (pinfunction "1_1") (pintype "passive"))
      (node (ref "R5") (pin "2") (pinfunction "2_2") (pintype "passive"))
    )
    (net (code "10") (name "Net-(Q1-D)") (class "Default")
      (node (ref "Q1") (pin "3") (pinfunction "D_3") (pintype "passive"))
      (node (ref "R4") (pin "2") (pinfunction "2_2") (pintype "passive"))
    )
    (net (code "11") (name "Net-(Q1-G)") (class "Default")
      (node (ref "D2") (pin "2") (pinfunction "2_2") (pintype "passive"))
      (node (ref "Q1") (pin "1") (pinfunction "G_1") (pintype "passive"))
      (node (ref "R6") (pin "1") (pinfunction "1_1") (pintype "passive"))
    )
    (net (code "12") (name "Net-(Q1-S)") (class "Default")
      (node (ref "D2") (pin "1") (pinfunction "1_1") (pintype "passive"))
      (node (ref "J3") (pin "2") (pinfunction "2_2") (pintype "passive"))
      (node (ref "Q1") (pin "2") (pinfunction "S_2") (pintype "passive"))
      (node (ref "R8") (pin "1") (pinfunction "1_1") (pintype "passive"))
      (node (ref "R9") (pin "1") (pinfunction "1_1") (pintype "passive"))
    )
    (net (code "13") (name "Net-(Q2-D)") (class "Default")
      (node (ref "C3") (pin "2") (pinfunction "2_2") (pintype "passive"))
      (node (ref "Q2") (pin "3") (pinfunction "D_3") (pintype "passive"))
      (node (ref "R5") (pin "1") (pinfunction "1_1") (pintype "passive"))
    )
    (net (code "14") (name "Net-(Q2-G)") (class "Default")
      (node (ref "Q2") (pin "1") (pinfunction "G_1") (pintype "passive"))
      (node (ref "R7") (pin "2") (pinfunction "2_2") (pintype "passive"))
    )
    (net (code "15") (name "Net-(Q3-D)") (class "Default")
      (node (ref "Q3") (pin "3") (pinfunction "D_3") (pintype "passive"))
      (node (ref "R9") (pin "2") (pinfunction "2_2") (pintype "passive"))
    )
    (net (code "16") (name "Net-(Q3-G)") (class "Default")
      (node (ref "D4") (pin "2") (pinfunction "2_2") (pintype "passive"))
      (node (ref "Q3") (pin "1") (pinfunction "G_1") (pintype "passive"))
      (node (ref "R10") (pin "1") (pinfunction "1_1") (pintype "passive"))
    )
    (net (code "17") (name "Net-(Q3-S)") (class "Default")
      (node (ref "D4") (pin "1") (pinfunction "1_1") (pintype "passive"))
      (node (ref "J3") (pin "3") (pinfunction "3_3") (pintype "passive"))
      (node (ref "Q3") (pin "2") (pinfunction "S_2") (pintype "passive"))
      (node (ref "R11") (pin "1") (pinfunction "1_1") (pintype "passive"))
      (node (ref "R12") (pin "1") (pinfunction "1_1") (pintype "passive"))
    )
    (net (code "18") (name "Net-(Q4-D)") (class "Default")
      (node (ref "Q4") (pin "3") (pinfunction "D_3") (pintype "passive"))
      (node (ref "R12") (pin "2") (pinfunction "2_2") (pintype "passive"))
    )
    (net (code "19") (name "Net-(Q4-G)") (class "Default")
      (node (ref "D6") (pin "2") (pinfunction "2_2") (pintype "passive"))
      (node (ref "Q4") (pin "1") (pinfunction "G_1") (pintype "passive"))
      (node (ref "R13") (pin "1") (pinfunction "1_1") (pintype "passive"))
    )
    (net (code "20") (name "Net-(Q4-S)") (class "Default")
      (node (ref "D6") (pin "1") (pinfunction "1_1") (pintype "passive"))
      (node (ref "J8") (pin "1") (pinfunction "1_1") (pintype "passive"))
      (node (ref "Q4") (pin "2") (pinfunction "S_2") (pintype "passive"))
      (node (ref "R14") (pin "1") (pinfunction "1_1") (pintype "passive"))
      (node (ref "R15") (pin "1") (pinfunction "1_1") (pintype "passive"))
    )
    (net (code "21") (name "Net-(Q5-D)") (class "Default")
      (node (ref "Q5") (pin "3") (pinfunction "D_3") (pintype "passive"))
      (node (ref "R15") (pin "2") (pinfunction "2_2") (pintype "passive"))
    )
    (net (code "22") (name "Net-(Q5-G)") (class "Default")
      (node (ref "D7") (pin "2") (pinfunction "2_2") (pintype "passive"))
      (node (ref "Q5") (pin "1") (pinfunction "G_1") (pintype "passive"))
      (node (ref "R16") (pin "1") (pinfunction "1_1") (pintype "passive"))
    )
    (net (code "23") (name "Net-(Q5-S)") (class "Default")
      (node (ref "D7") (pin "1") (pinfunction "1_1") (pintype "passive"))
      (node (ref "J8") (pin "2") (pinfunction "2_2") (pintype "passive"))
      (node (ref "Q5") (pin "2") (pinfunction "S_2") (pintype "passive"))
      (node (ref "R17") (pin "1") (pinfunction "1_1") (pintype "passive"))
      (node (ref "R18") (pin "1") (pinfunction "1_1") (pintype "passive"))
      (node (ref "R19") (pin "1") (pinfunction "1_1") (pintype "passive"))
      (node (ref "R20") (pin "1") (pinfunction "1_1") (pintype "passive"))
    )
    (net (code "24") (name "Net-(Q6-D)") (class "Default")
      (node (ref "Q6") (pin "3") (pinfunction "D_3") (pintype "passive"))
      (node (ref "R20") (pin "2") (pinfunction "2_2") (pintype "passive"))
    )
    (net (code "25") (name "Net-(Q6-G)") (class "Default")
      (node (ref "D8") (pin "2") (pinfunction "2_2") (pintype "passive"))
      (node (ref "Q6") (pin "1") (pinfunction "G_1") (pintype "passive"))
      (node (ref "R21") (pin "1") (pinfunction "1_1") (pintype "passive"))
    )
    (net (code "26") (name "Net-(Q6-S)") (class "Default")
      (node (ref "D8") (pin "1") (pinfunction "1_1") (pintype "passive"))
      (node (ref "J8") (pin "3") (pinfunction "3_3") (pintype "passive"))
      (node (ref "Q6") (pin "2") (pinfunction "S_2") (pintype "passive"))
      (node (ref "R25") (pin "1") (pinfunction "1_1") (pintype "passive"))
      (node (ref "R26") (pin "1") (pinfunction "1_1") (pintype "passive"))
    )
    (net (code "27") (name "Net-(Q7-D)") (class "Default")
      (node (ref "Q7") (pin "3") (pinfunction "D_3") (pintype "passive"))
      (node (ref "R25") (pin "2") (pinfunction "2_2") (pintype "passive"))
    )
    (net (code "28") (name "Net-(Q7-G)") (class "Default")
      (node (ref "D9") (pin "2") (pinfunction "2_2") (pintype "passive"))
      (node (ref "Q7") (pin "1") (pinfunction "G_1") (pintype "passive"))
      (node (ref "R27") (pin "1") (pinfunction "1_1") (pintype "passive"))
    )
    (net (code "29") (name "Net-(Q7-S)") (class "Default")
      (node (ref "D9") (pin "1") (pinfunction "1_1") (pintype "passive"))
      (node (ref "J9") (pin "1") (pinfunction "1_1") (pintype "passive"))
      (node (ref "Q7") (pin "2") (pinfunction "S_2") (pintype "passive"))
      (node (ref "R28") (pin "1") (pinfunction "1_1") (pintype "passive"))
      (node (ref "R29") (pin "1") (pinfunction "1_1") (pintype "passive"))
    )
    (net (code "30") (name "Net-(Q8-D)") (class "Default")
      (node (ref "Q8") (pin "3") (pinfunction "D_3") (pintype "passive"))
      (node (ref "R29") (pin "2") (pinfunction "2_2") (pintype "passive"))
    )
    (net (code "31") (name "Net-(Q8-G)") (class "Default")
      (node (ref "D10") (pin "2") (pinfunction "2_2") (pintype "passive"))
      (node (ref "Q8") (pin "1") (pinfunction "G_1") (pintype "passive"))
      (node (ref "R31") (pin "1") (pinfunction "1_1") (pintype "passive"))
    )
    (net (code "32") (name "Net-(Q8-S)") (class "Default")
      (node (ref "D10") (pin "1") (pinfunction "1_1") (pintype "passive"))
      (node (ref "J9") (pin "2") (pinfunction "2_2") (pintype "passive"))
      (node (ref "Q8") (pin "2") (pinfunction "S_2") (pintype "passive"))
      (node (ref "R32") (pin "1") (pinfunction "1_1") (pintype "passive"))
      (node (ref "R33") (pin "1") (pinfunction "1_1") (pintype "passive"))
    )
    (net (code "33") (name "Net-(Q9-D)") (class "Default")
      (node (ref "Q9") (pin "3") (pinfunction "D_3") (pintype "passive"))
      (node (ref "R33") (pin "2") (pinfunction "2_2") (pintype "passive"))
    )
    (net (code "34") (name "Net-(Q9-G)") (class "Default")
      (node (ref "D11") (pin "2") (pinfunction "2_2") (pintype "passive"))
      (node (ref "Q9") (pin "1") (pinfunction "G_1") (pintype "passive"))
      (node (ref "R34") (pin "1") (pinfunction "1_1") (pintype "passive"))
    )
    (net (code "35") (name "Net-(Q10-D)") (class "Default")
      (node (ref "Q10") (pin "3") (pinfunction "D_3") (pintype "passive"))
      (node (ref "R36") (pin "2") (pinfunction "2_2") (pintype "passive"))
    )
    (net (code "36") (name "Net-(Q10-G)") (class "Default")
      (node (ref "D12") (pin "2") (pinfunction "2_2") (pintype "passive"))
      (node (ref "Q10") (pin "1") (pinfunction "G_1") (pintype "passive"))
      (node (ref "R37") (pin "1") (pinfunction "1_1") (pintype "passive"))
    )
    (net (code "37") (name "Net-(Q10-S)") (class "Default")
      (node (ref "D12") (pin "1") (pinfunction "1_1") (pintype "passive"))
      (node (ref "J9") (pin "4") (pinfunction "4_4") (pintype "passive"))
      (node (ref "Q10") (pin "2") (pinfunction "S_2") (pintype "passive"))
      (node (ref "R38") (pin "1") (pinfunction "1_1") (pintype "passive"))
    )
    (net (code "38") (name "Net-(R24-Pad1)") (class "Default")
      (node (ref "R24") (pin "1") (pinfunction "1_1") (pintype "passive"))
      (node (ref "S1") (pin "B1") (pinfunction "B1_B1") (pintype "passive"))
      (node (ref "S1") (pin "B2") (pinfunction "B2_B2") (pintype "passive"))
    )
    (net (code "39") (name "Net-(U1-TS1)") (class "Default")
      (node (ref "C13") (pin "2") (pinfunction "2_2") (pintype "passive"))
      (node (ref "RT2") (pin "2") (pinfunction "2_2") (pintype "passive"))
      (node (ref "S1") (pin "A1") (pinfunction "A1_A1") (pintype "passive"))
      (node (ref "S1") (pin "A2") (pinfunction "A2_A2") (pintype "passive"))
      (node (ref "U1") (pin "6") (pinfunction "TS1_6") (pintype "input"))
    )
    (net (code "40") (name "Net-(U1-TS2)") (class "Default")
      (node (ref "C9") (pin "2") (pinfunction "2_2") (pintype "passive"))
      (node (ref "RT1") (pin "2") (pinfunction "2_2") (pintype "passive"))
      (node (ref "U1") (pin "13") (pinfunction "TS2_13") (pintype "input"))
    )
    (net (code "41") (name "Net-(U1-VC0)") (class "Default")
      (node (ref "C20") (pin "1") (pinfunction "1_1") (pintype "passive"))
      (node (ref "C21") (pin "2") (pinfunction "2_2") (pintype "passive"))
      (node (ref "R37") (pin "2") (pinfunction "2_2") (pintype "passive"))
      (node (ref "R38") (pin "2") (pinfunction "2_2") (pintype "passive"))
      (node (ref "U1") (pin "27") (pinfunction "VC0_27") (pintype "input"))
    )
    (net (code "42") (name "Net-(U1-VC1)") (class "Default")
      (node (ref "C19") (pin "1") (pinfunction "1_1") (pintype "passive"))
      (node (ref "C20") (pin "2") (pinfunction "2_2") (pintype "passive"))
      (node (ref "R34") (pin "2") (pinfunction "2_2") (pintype "passive"))
      (node (ref "R35") (pin "2") (pinfunction "2_2") (pintype "passive"))
      (node (ref "U1") (pin "26") (pinfunction "VC1_26") (pintype "input"))
    )
    (net (code "43") (name "Net-(U1-VC2)") (class "Default")
      (node (ref "C18") (pin "1") (pinfunction "1_1") (pintype "passive"))
      (node (ref "C19") (pin "2") (pinfunction "2_2") (pintype "passive"))
      (node (ref "R31") (pin "2") (pinfunction "2_2") (pintype "passive"))
      (node (ref "R32") (pin "2") (pinfunction "2_2") (pintype "passive"))
      (node (ref "U1") (pin "25") (pinfunction "VC2_25") (pintype "input"))
    )
    (net (code "44") (name "Net-(U1-VC3)") (class "Default")
      (node (ref "C16") (pin "1") (pinfunction "1_1") (pintype "passive"))
      (node (ref "C18") (pin "2") (pinfunction "2_2") (pintype "passive"))
      (node (ref "R27") (pin "2") (pinfunction "2_2") (pintype "passive"))
      (node (ref "R28") (pin "2") (pinfunction "2_2") (pintype "passive"))
      (node (ref "U1") (pin "24") (pinfunction "VC3_24") (pintype "input"))
    )
    (net (code "45") (name "Net-(U1-VC4)") (class "Default")
      (node (ref "C14") (pin "1") (pinfunction "1_1") (pintype "passive"))
      (node (ref "C16") (pin "2") (pinfunction "2_2") (pintype "passive"))
      (node (ref "R21") (pin "2") (pinfunction "2_2") (pintype "passive"))
      (node (ref "R26") (pin "2") (pinfunction "2_2") (pintype "passive"))
      (node (ref "U1") (pin "23") (pinfunction "VC4_23") (pintype "input"))
    )
    (net (code "46") (name "Net-(U1-VC5)") (class "Default")
      (node (ref "C14") (pin "2") (pinfunction "2_2") (pintype "passive"))
      (node (ref "D3") (pin "1") (pinfunction "1_1") (pintype "passive"))
      (node (ref "R19") (pin "2") (pinfunction "2_2") (pintype "passive"))
      (node (ref "U1") (pin "22") (pinfunction "VC5_22") (pintype "input"))
    )
    (net (code "47") (name "Net-(U1-VC5B)") (class "Default")
      (node (ref "C11") (pin "2") (pinfunction "2_2") (pintype "passive"))
      (node (ref "R16") (pin "2") (pinfunction "2_2") (pintype "passive"))
      (node (ref "R17") (pin "2") (pinfunction "2_2") (pintype "passive"))
      (node (ref "U1") (pin "21") (pinfunction "VC5B_21") (pintype "input"))
    )
    (net (code "48") (name "Net-(U1-VC6)") (class "Default")
      (node (ref "C7") (pin "1") (pinfunction "1_1") (pintype "passive"))
      (node (ref "C8") (pin "2") (pinfunction "2_2") (pintype "passive"))
      (node (ref "R13") (pin "2") (pinfunction "2_2") (pintype "passive"))
      (node (ref "R14") (pin "2") (pinfunction "2_2") (pintype "passive"))
      (node (ref "U1") (pin "20") (pinfunction "VC6_20") (pintype "input"))
    )
    (net (code "49") (name "Net-(U1-VC7)") (class "Default")
      (node (ref "C4") (pin "1") (pinfunction "1_1") (pintype "passive"))
      (node (ref "C7") (pin "2") (pinfunction "2_2") (pintype "passive"))
      (node (ref "R10") (pin "2") (pinfunction "2_2") (pintype "passive"))
      (node (ref "R11") (pin "2") (pinfunction "2_2") (pintype "passive"))
      (node (ref "U1") (pin "19") (pinfunction "VC7_19") (pintype "input"))
    )
    (net (code "50") (name "Net-(U1-VC8)") (class "Default")
      (node (ref "C1") (pin "1") (pinfunction "1_1") (pintype "passive"))
      (node (ref "C4") (pin "2") (pinfunction "2_2") (pintype "passive"))
      (node (ref "R6") (pin "2") (pinfunction "2_2") (pintype "passive"))
      (node (ref "R8") (pin "2") (pinfunction "2_2") (pintype "passive"))
      (node (ref "U1") (pin "17") (pinfunction "VC9_17") (pintype "input"))
      (node (ref "U1") (pin "18") (pinfunction "VC8_18") (pintype "input"))
    )
    (net (code "51") (name "Net-(U1-VC10)") (class "Default")
      (node (ref "C1") (pin "2") (pinfunction "2_2") (pintype "passive"))
      (node (ref "D5") (pin "1") (pinfunction "1_1") (pintype "passive"))
      (node (ref "R3") (pin "2") (pinfunction "2_2") (pintype "passive"))
      (node (ref "U1") (pin "16") (pinfunction "VC10_16") (pintype "input"))
    )
    (net (code "52") (name "REGOUT") (class "Default")
      (node (ref "C12") (pin "2") (pinfunction "2_2") (pintype "passive"))
      (node (ref "R22") (pin "2") (pinfunction "2_2") (pintype "passive"))
      (node (ref "R23") (pin "2") (pinfunction "2_2") (pintype "passive"))
      (node (ref "U1") (pin "8") (pinfunction "REGOUT_8") (pintype "power_in"))
    )
    (net (code "53") (name "REGSRC") (class "Default")
      (node (ref "C6") (pin "2") (pinfunction "2_2") (pintype "passive"))
      (node (ref "Q2") (pin "2") (pinfunction "S_2") (pintype "passive"))
      (node (ref "U1") (pin "9") (pinfunction "REGSRC_9") (pintype "power_in"))
    )
    (net (code "54") (name "SCL") (class "Default")
      (node (ref "R23") (pin "1") (pinfunction "1_1") (pintype "passive"))
      (node (ref "U1") (pin "5") (pinfunction "SCL_5") (pintype "bidirectional"))
    )
    (net (code "55") (name "SDA") (class "Default")
      (node (ref "R22") (pin "1") (pinfunction "1_1") (pintype "passive"))
      (node (ref "U1") (pin "4") (pinfunction "SDA_4") (pintype "bidirectional"))
    )
    (net (code "56") (name "SRN") (class "Default")
      (node (ref "U1") (pin "29") (pinfunction "SRN_29") (pintype "input"))
    )
    (net (code "57") (name "SRP") (class "Default")
      (node (ref "U1") (pin "28") (pinfunction "SRP_28") (pintype "input"))
    )
    (net (code "58") (name "VC5X") (class "Default")
      (node (ref "C10") (pin "2") (pinfunction "2_2") (pintype "passive"))
      (node (ref "C11") (pin "1") (pinfunction "1_1") (pintype "passive"))
      (node (ref "C2") (pin "1") (pinfunction "1_1") (pintype "passive"))
      (node (ref "C5") (pin "2") (pinfunction "2_2") (pintype "passive"))
      (node (ref "C8") (pin "1") (pinfunction "1_1") (pintype "passive"))
      (node (ref "C9") (pin "1") (pinfunction "1_1") (pintype "passive"))
      (node (ref "D3") (pin "2") (pinfunction "2_2") (pintype "passive"))
      (node (ref "R18") (pin "2") (pinfunction "2_2") (pintype "passive"))
      (node (ref "R7") (pin "1") (pinfunction "1_1") (pintype "passive"))
      (node (ref "RT1") (pin "1") (pinfunction "1_1") (pintype "passive"))
      (node (ref "U1") (pin "10") (pinfunction "VC5X_10") (pintype "input"))
    )
    (net (code "59") (name "VC10X") (class "Default")
      (node (ref "C2") (pin "2") (pinfunction "2_2") (pintype "passive"))
      (node (ref "D5") (pin "2") (pinfunction "2_2") (pintype "passive"))
      (node (ref "R1") (pin "1") (pinfunction "1_1") (pintype "passive"))
      (node (ref "U1") (pin "15") (pinfunction "BAT_15") (pintype "power_in"))
    )
    (net (code "60") (name "unconnected-(J3-MNT_1-Pad5)") (class "Default")
      (node (ref "J3") (pin "5") (pinfunction "MNT_1_5") (pintype "passive"))
    )
    (net (code "61") (name "unconnected-(J3-MNT_2-Pad6)") (class "Default")
      (node (ref "J3") (pin "6") (pinfunction "MNT_2_6") (pintype "passive"))
    )
    (net (code "62") (name "unconnected-(J3-Pad4)") (class "Default")
      (node (ref "J3") (pin "4") (pinfunction "4_4") (pintype "passive+no_connect"))
    )
    (net (code "63") (name "unconnected-(J8-MNT_1-Pad5)") (class "Default")
      (node (ref "J8") (pin "5") (pinfunction "MNT_1_5") (pintype "passive"))
    )
    (net (code "64") (name "unconnected-(J8-MNT_2-Pad6)") (class "Default")
      (node (ref "J8") (pin "6") (pinfunction "MNT_2_6") (pintype "passive"))
    )
    (net (code "65") (name "unconnected-(J8-Pad4)") (class "Default")
      (node (ref "J8") (pin "4") (pinfunction "4_4") (pintype "passive+no_connect"))
    )
    (net (code "66") (name "unconnected-(J9-MNT_1-Pad5)") (class "Default")
      (node (ref "J9") (pin "5") (pinfunction "MNT_1_5") (pintype "passive"))
    )
    (net (code "67") (name "unconnected-(J9-MNT_2-Pad6)") (class "Default")
      (node (ref "J9") (pin "6") (pinfunction "MNT_2_6") (pintype "passive"))
    )
  )
)
